# greedy_large.net
KiCad netlist of a schematic drawn in EAGLE
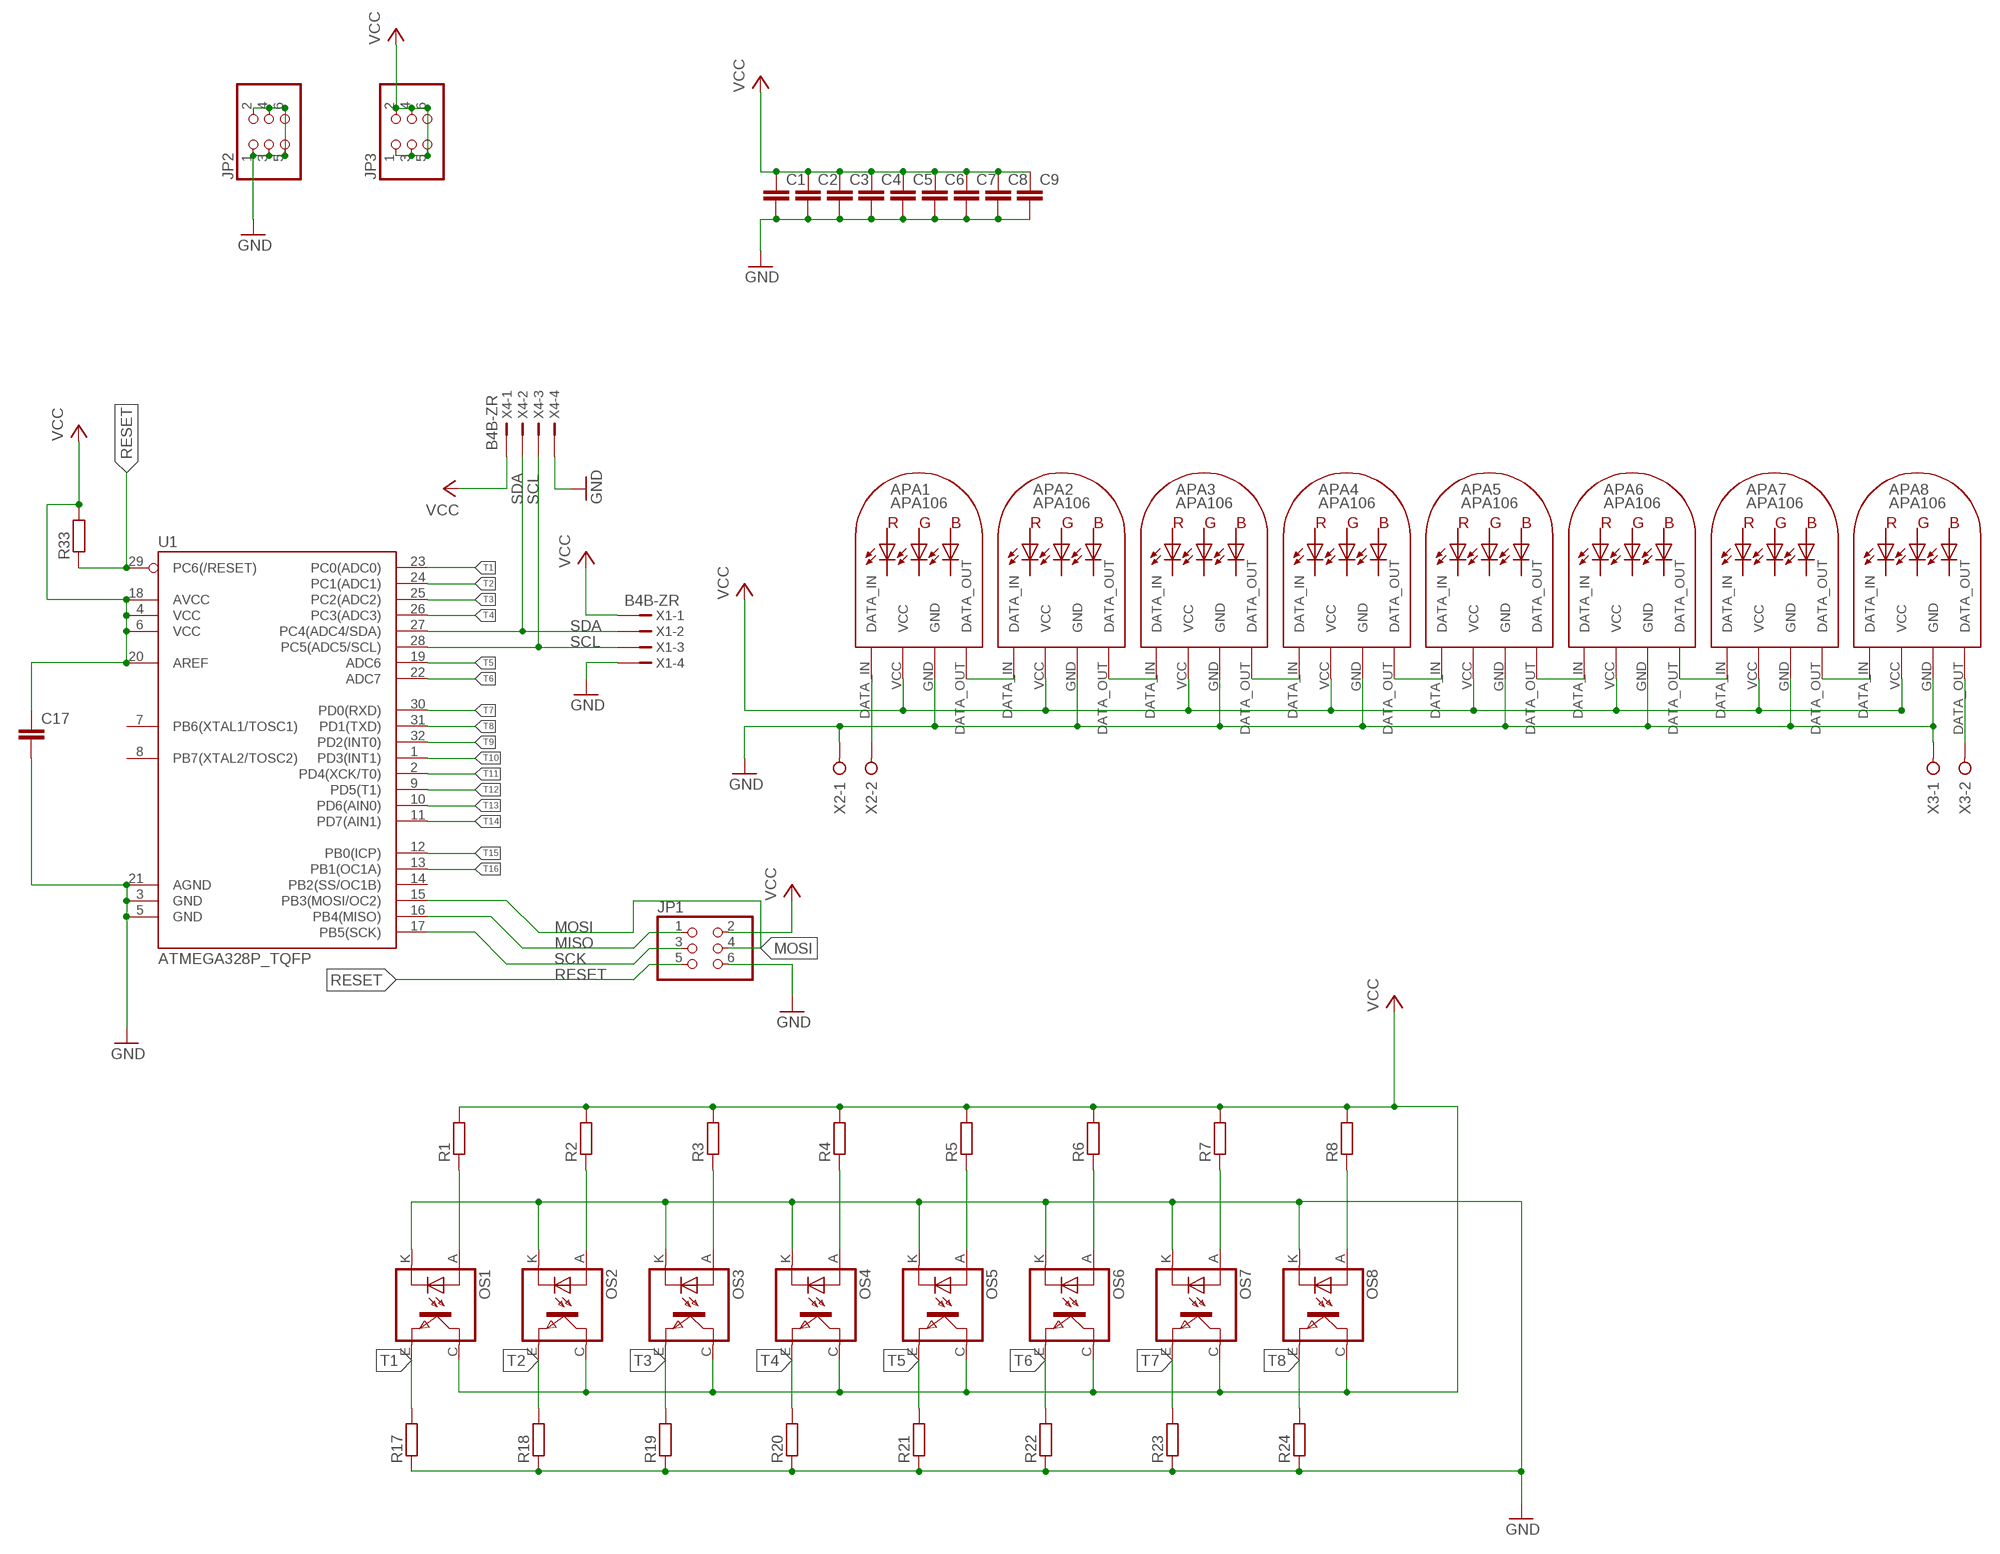
[diagram p0: schematic, sheet 1]

(export (version "E")
  (design (tool "Eeschema 10.0.6"))
  (components
    (comp (ref "APA1")
      (value "APA106")
      (footprint "eagle-import:APA_106_8MM")
      (libsource (lib "eagle-import") (part "APA106"))
    )
    (comp (ref "APA2")
      (value "APA106")
      (footprint "eagle-import:APA_106_8MM")
      (libsource (lib "eagle-import") (part "APA106"))
    )
    (comp (ref "APA3")
      (value "APA106")
      (footprint "eagle-import:APA_106_8MM")
      (libsource (lib "eagle-import") (part "APA106"))
    )
    (comp (ref "APA4")
      (value "APA106")
      (footprint "eagle-import:APA_106_8MM")
      (libsource (lib "eagle-import") (part "APA106"))
    )
    (comp (ref "APA5")
      (value "APA106")
      (footprint "eagle-import:APA_106_8MM")
      (libsource (lib "eagle-import") (part "APA106"))
    )
    (comp (ref "APA6")
      (value "APA106")
      (footprint "eagle-import:APA_106_8MM")
      (libsource (lib "eagle-import") (part "APA106"))
    )
    (comp (ref "APA7")
      (value "APA106")
      (footprint "eagle-import:APA_106_8MM")
      (libsource (lib "eagle-import") (part "APA106"))
    )
    (comp (ref "APA8")
      (value "APA106")
      (footprint "eagle-import:APA_106_8MM")
      (libsource (lib "eagle-import") (part "APA106"))
    )
    (comp (ref "C1")
      (value "C5/3")
      (footprint "eagle-import:C5B3")
      (libsource (lib "eagle-import") (part "C5/3"))
    )
    (comp (ref "C2")
      (value "C5/3")
      (footprint "eagle-import:C5B3")
      (libsource (lib "eagle-import") (part "C5/3"))
    )
    (comp (ref "C3")
      (value "C5/3")
      (footprint "eagle-import:C5B3")
      (libsource (lib "eagle-import") (part "C5/3"))
    )
    (comp (ref "C4")
      (value "C5/3")
      (footprint "eagle-import:C5B3")
      (libsource (lib "eagle-import") (part "C5/3"))
    )
    (comp (ref "C5")
      (value "C5/3")
      (footprint "eagle-import:C5B3")
      (libsource (lib "eagle-import") (part "C5/3"))
    )
    (comp (ref "C6")
      (value "C5/3")
      (footprint "eagle-import:C5B3")
      (libsource (lib "eagle-import") (part "C5/3"))
    )
    (comp (ref "C7")
      (value "C5/3")
      (footprint "eagle-import:C5B3")
      (libsource (lib "eagle-import") (part "C5/3"))
    )
    (comp (ref "C8")
      (value "C5/3")
      (footprint "eagle-import:C5B3")
      (libsource (lib "eagle-import") (part "C5/3"))
    )
    (comp (ref "C9")
      (value "C5/3")
      (footprint "eagle-import:C5B3")
      (libsource (lib "eagle-import") (part "C5/3"))
    )
    (comp (ref "C17")
      (value "C-EU025-025X050")
      (footprint "eagle-import:C025-025X050")
      (libsource (lib "eagle-import") (part "C-EU025-025X050"))
    )
    (comp (ref "JP1")
      (value "PINHD-2X3")
      (footprint "eagle-import:2X03")
      (libsource (lib "eagle-import") (part "PINHD-2X3"))
    )
    (comp (ref "JP2")
      (value "PINHD-2X3")
      (footprint "eagle-import:2X03")
      (libsource (lib "eagle-import") (part "PINHD-2X3"))
    )
    (comp (ref "JP3")
      (value "PINHD-2X3")
      (footprint "eagle-import:2X03")
      (libsource (lib "eagle-import") (part "PINHD-2X3"))
    )
    (comp (ref "OS1")
      (value "TCRT5000")
      (footprint "eagle-import:TCRT5000")
      (libsource (lib "eagle-import") (part "TCRT5000"))
    )
    (comp (ref "OS2")
      (value "TCRT5000")
      (footprint "eagle-import:TCRT5000")
      (libsource (lib "eagle-import") (part "TCRT5000"))
    )
    (comp (ref "OS3")
      (value "TCRT5000")
      (footprint "eagle-import:TCRT5000")
      (libsource (lib "eagle-import") (part "TCRT5000"))
    )
    (comp (ref "OS4")
      (value "TCRT5000")
      (footprint "eagle-import:TCRT5000")
      (libsource (lib "eagle-import") (part "TCRT5000"))
    )
    (comp (ref "OS5")
      (value "TCRT5000")
      (footprint "eagle-import:TCRT5000")
      (libsource (lib "eagle-import") (part "TCRT5000"))
    )
    (comp (ref "OS6")
      (value "TCRT5000")
      (footprint "eagle-import:TCRT5000")
      (libsource (lib "eagle-import") (part "TCRT5000"))
    )
    (comp (ref "OS7")
      (value "TCRT5000")
      (footprint "eagle-import:TCRT5000")
      (libsource (lib "eagle-import") (part "TCRT5000"))
    )
    (comp (ref "OS8")
      (value "TCRT5000")
      (footprint "eagle-import:TCRT5000")
      (libsource (lib "eagle-import") (part "TCRT5000"))
    )
    (comp (ref "R1")
      (value "R-EU_R0805")
      (footprint "eagle-import:R0805")
      (libsource (lib "eagle-import") (part "R-EU_R0805"))
    )
    (comp (ref "R2")
      (value "R-EU_R0805")
      (footprint "eagle-import:R0805")
      (libsource (lib "eagle-import") (part "R-EU_R0805"))
    )
    (comp (ref "R3")
      (value "R-EU_R0805")
      (footprint "eagle-import:R0805")
      (libsource (lib "eagle-import") (part "R-EU_R0805"))
    )
    (comp (ref "R4")
      (value "R-EU_R0805")
      (footprint "eagle-import:R0805")
      (libsource (lib "eagle-import") (part "R-EU_R0805"))
    )
    (comp (ref "R5")
      (value "R-EU_R0805")
      (footprint "eagle-import:R0805")
      (libsource (lib "eagle-import") (part "R-EU_R0805"))
    )
    (comp (ref "R6")
      (value "R-EU_R0805")
      (footprint "eagle-import:R0805")
      (libsource (lib "eagle-import") (part "R-EU_R0805"))
    )
    (comp (ref "R7")
      (value "R-EU_R0805")
      (footprint "eagle-import:R0805")
      (libsource (lib "eagle-import") (part "R-EU_R0805"))
    )
    (comp (ref "R8")
      (value "R-EU_R0805")
      (footprint "eagle-import:R0805")
      (libsource (lib "eagle-import") (part "R-EU_R0805"))
    )
    (comp (ref "R17")
      (value "R-EU_R0805")
      (footprint "eagle-import:R0805")
      (libsource (lib "eagle-import") (part "R-EU_R0805"))
    )
    (comp (ref "R18")
      (value "R-EU_R0805")
      (footprint "eagle-import:R0805")
      (libsource (lib "eagle-import") (part "R-EU_R0805"))
    )
    (comp (ref "R19")
      (value "R-EU_R0805")
      (footprint "eagle-import:R0805")
      (libsource (lib "eagle-import") (part "R-EU_R0805"))
    )
    (comp (ref "R20")
      (value "R-EU_R0805")
      (footprint "eagle-import:R0805")
      (libsource (lib "eagle-import") (part "R-EU_R0805"))
    )
    (comp (ref "R21")
      (value "R-EU_R0805")
      (footprint "eagle-import:R0805")
      (libsource (lib "eagle-import") (part "R-EU_R0805"))
    )
    (comp (ref "R22")
      (value "R-EU_R0805")
      (footprint "eagle-import:R0805")
      (libsource (lib "eagle-import") (part "R-EU_R0805"))
    )
    (comp (ref "R23")
      (value "R-EU_R0805")
      (footprint "eagle-import:R0805")
      (libsource (lib "eagle-import") (part "R-EU_R0805"))
    )
    (comp (ref "R24")
      (value "R-EU_R0805")
      (footprint "eagle-import:R0805")
      (libsource (lib "eagle-import") (part "R-EU_R0805"))
    )
    (comp (ref "R33")
      (value "R-EU_R0805")
      (footprint "eagle-import:R0805")
      (libsource (lib "eagle-import") (part "R-EU_R0805"))
    )
    (comp (ref "U1")
      (value "ATMEGA328P_TQFP")
      (footprint "eagle-import:TQFP32-08")
      (libsource (lib "eagle-import") (part "ATMEGA328P_TQFP"))
    )
    (comp (ref "X1")
      (value "B4B-ZR")
      (footprint "eagle-import:B4B-ZR")
      (fields (field (name "MF") "FARNELL") (field (name "MPN") "B4B-ZR(LF)(SN)"))
      (libsource (lib "eagle-import") (part "?4B-ZRB"))
    )
    (comp (ref "X2")
      (value "W237-02P")
      (footprint "eagle-import:W237-132")
      (libsource (lib "eagle-import") (part "W237-02P"))
    )
    (comp (ref "X3")
      (value "W237-02P")
      (footprint "eagle-import:W237-132")
      (libsource (lib "eagle-import") (part "W237-02P"))
    )
    (comp (ref "X4")
      (value "B4B-ZR")
      (footprint "eagle-import:B4B-ZR")
      (fields (field (name "MF") "FARNELL") (field (name "MPN") "B4B-ZR(LF)(SN)"))
      (libsource (lib "eagle-import") (part "?4B-ZRB"))
    )
  )
  (nets
    (net (code "1") (name "/MISO") (class "Default")
      (node (ref "JP1") (pin "1") (pinfunction "1_1") (pintype "passive"))
      (node (ref "U1") (pin "16") (pinfunction "PB4(MISO)_16") (pintype "bidirectional"))
    )
    (net (code "2") (name "/SCK") (class "Default")
      (node (ref "JP1") (pin "3") (pinfunction "3_3") (pintype "passive"))
      (node (ref "U1") (pin "17") (pinfunction "PB5(SCK)_17") (pintype "bidirectional"))
    )
    (net (code "3") (name "/SCL") (class "Default")
      (node (ref "U1") (pin "28") (pinfunction "PC5(ADC5/SCL)_28") (pintype "bidirectional"))
      (node (ref "X1") (pin "3") (pinfunction "1_3") (pintype "passive"))
      (node (ref "X4") (pin "3") (pinfunction "1_3") (pintype "passive"))
    )
    (net (code "4") (name "/SDA") (class "Default")
      (node (ref "U1") (pin "27") (pinfunction "PC4(ADC4/SDA)_27") (pintype "bidirectional"))
      (node (ref "X1") (pin "2") (pinfunction "1_2") (pintype "passive"))
      (node (ref "X4") (pin "2") (pinfunction "1_2") (pintype "passive"))
    )
    (net (code "5") (name "GND") (class "Default")
      (node (ref "APA1") (pin "GND") (pinfunction "GND_GND") (pintype "power_in"))
      (node (ref "APA2") (pin "GND") (pinfunction "GND_GND") (pintype "power_in"))
      (node (ref "APA3") (pin "GND") (pinfunction "GND_GND") (pintype "power_in"))
      (node (ref "APA4") (pin "GND") (pinfunction "GND_GND") (pintype "power_in"))
      (node (ref "APA5") (pin "GND") (pinfunction "GND_GND") (pintype "power_in"))
      (node (ref "APA6") (pin "GND") (pinfunction "GND_GND") (pintype "power_in"))
      (node (ref "APA7") (pin "GND") (pinfunction "GND_GND") (pintype "power_in"))
      (node (ref "APA8") (pin "GND") (pinfunction "GND_GND") (pintype "power_in"))
      (node (ref "C1") (pin "2") (pinfunction "2_2") (pintype "passive"))
      (node (ref "C17") (pin "2") (pinfunction "2_2") (pintype "passive"))
      (node (ref "C2") (pin "2") (pinfunction "2_2") (pintype "passive"))
      (node (ref "C3") (pin "2") (pinfunction "2_2") (pintype "passive"))
      (node (ref "C4") (pin "2") (pinfunction "2_2") (pintype "passive"))
      (node (ref "C5") (pin "2") (pinfunction "2_2") (pintype "passive"))
      (node (ref "C6") (pin "2") (pinfunction "2_2") (pintype "passive"))
      (node (ref "C7") (pin "2") (pinfunction "2_2") (pintype "passive"))
      (node (ref "C8") (pin "2") (pinfunction "2_2") (pintype "passive"))
      (node (ref "C9") (pin "2") (pinfunction "2_2") (pintype "passive"))
      (node (ref "JP1") (pin "6") (pinfunction "6_6") (pintype "passive"))
      (node (ref "JP2") (pin "1") (pinfunction "1_1") (pintype "passive"))
      (node (ref "JP2") (pin "2") (pinfunction "2_2") (pintype "passive"))
      (node (ref "JP2") (pin "3") (pinfunction "3_3") (pintype "passive"))
      (node (ref "JP2") (pin "4") (pinfunction "4_4") (pintype "passive"))
      (node (ref "JP2") (pin "5") (pinfunction "5_5") (pintype "passive"))
      (node (ref "JP2") (pin "6") (pinfunction "6_6") (pintype "passive"))
      (node (ref "OS1") (pin "K") (pinfunction "CATHODE_K") (pintype "passive"))
      (node (ref "OS2") (pin "K") (pinfunction "CATHODE_K") (pintype "passive"))
      (node (ref "OS3") (pin "K") (pinfunction "CATHODE_K") (pintype "passive"))
      (node (ref "OS4") (pin "K") (pinfunction "CATHODE_K") (pintype "passive"))
      (node (ref "OS5") (pin "K") (pinfunction "CATHODE_K") (pintype "passive"))
      (node (ref "OS6") (pin "K") (pinfunction "CATHODE_K") (pintype "passive"))
      (node (ref "OS7") (pin "K") (pinfunction "CATHODE_K") (pintype "passive"))
      (node (ref "OS8") (pin "K") (pinfunction "CATHODE_K") (pintype "passive"))
      (node (ref "R17") (pin "1") (pinfunction "1_1") (pintype "passive"))
      (node (ref "R17") (pin "11") (pinfunction "1_11") (pintype "passive"))
      (node (ref "R18") (pin "1") (pinfunction "1_1") (pintype "passive"))
      (node (ref "R18") (pin "11") (pinfunction "1_11") (pintype "passive"))
      (node (ref "R19") (pin "1") (pinfunction "1_1") (pintype "passive"))
      (node (ref "R19") (pin "11") (pinfunction "1_11") (pintype "passive"))
      (node (ref "R20") (pin "1") (pinfunction "1_1") (pintype "passive"))
      (node (ref "R20") (pin "11") (pinfunction "1_11") (pintype "passive"))
      (node (ref "R21") (pin "1") (pinfunction "1_1") (pintype "passive"))
      (node (ref "R21") (pin "11") (pinfunction "1_11") (pintype "passive"))
      (node (ref "R22") (pin "1") (pinfunction "1_1") (pintype "passive"))
      (node (ref "R22") (pin "11") (pinfunction "1_11") (pintype "passive"))
      (node (ref "R23") (pin "1") (pinfunction "1_1") (pintype "passive"))
      (node (ref "R23") (pin "11") (pinfunction "1_11") (pintype "passive"))
      (node (ref "R24") (pin "1") (pinfunction "1_1") (pintype "passive"))
      (node (ref "R24") (pin "11") (pinfunction "1_11") (pintype "passive"))
      (node (ref "U1") (pin "21") (pinfunction "AGND_21") (pintype "bidirectional"))
      (node (ref "U1") (pin "3") (pinfunction "GND_3") (pintype "bidirectional"))
      (node (ref "U1") (pin "5") (pinfunction "GND_5") (pintype "bidirectional"))
      (node (ref "X1") (pin "4") (pinfunction "1_4") (pintype "passive"))
      (node (ref "X2") (pin "1") (pinfunction "KL_1") (pintype "passive"))
      (node (ref "X3") (pin "1") (pinfunction "KL_1") (pintype "passive"))
      (node (ref "X4") (pin "4") (pinfunction "1_4") (pintype "passive"))
    )
    (net (code "6") (name "MOSI") (class "Default")
      (node (ref "JP1") (pin "4") (pinfunction "4_4") (pintype "passive"))
      (node (ref "U1") (pin "15") (pinfunction "PB3(MOSI/OC2)_15") (pintype "bidirectional"))
    )
    (net (code "7") (name "Net-(APA1-PadDATA_OUT)") (class "Default")
      (node (ref "APA1") (pin "DATA_OUT") (pinfunction "DATA_OUT_DATA_OUT") (pintype "bidirectional"))
      (node (ref "APA2") (pin "DATA_IN") (pinfunction "DATA_IN_DATA_IN") (pintype "bidirectional"))
    )
    (net (code "8") (name "Net-(APA2-PadDATA_OUT)") (class "Default")
      (node (ref "APA2") (pin "DATA_OUT") (pinfunction "DATA_OUT_DATA_OUT") (pintype "bidirectional"))
      (node (ref "APA3") (pin "DATA_IN") (pinfunction "DATA_IN_DATA_IN") (pintype "bidirectional"))
    )
    (net (code "9") (name "Net-(APA3-PadDATA_OUT)") (class "Default")
      (node (ref "APA3") (pin "DATA_OUT") (pinfunction "DATA_OUT_DATA_OUT") (pintype "bidirectional"))
      (node (ref "APA4") (pin "DATA_IN") (pinfunction "DATA_IN_DATA_IN") (pintype "bidirectional"))
    )
    (net (code "10") (name "Net-(APA4-PadDATA_OUT)") (class "Default")
      (node (ref "APA4") (pin "DATA_OUT") (pinfunction "DATA_OUT_DATA_OUT") (pintype "bidirectional"))
      (node (ref "APA5") (pin "DATA_IN") (pinfunction "DATA_IN_DATA_IN") (pintype "bidirectional"))
    )
    (net (code "11") (name "Net-(APA5-PadDATA_OUT)") (class "Default")
      (node (ref "APA5") (pin "DATA_OUT") (pinfunction "DATA_OUT_DATA_OUT") (pintype "bidirectional"))
      (node (ref "APA6") (pin "DATA_IN") (pinfunction "DATA_IN_DATA_IN") (pintype "bidirectional"))
    )
    (net (code "12") (name "Net-(APA6-PadDATA_OUT)") (class "Default")
      (node (ref "APA6") (pin "DATA_OUT") (pinfunction "DATA_OUT_DATA_OUT") (pintype "bidirectional"))
      (node (ref "APA7") (pin "DATA_IN") (pinfunction "DATA_IN_DATA_IN") (pintype "bidirectional"))
    )
    (net (code "13") (name "Net-(APA7-PadDATA_OUT)") (class "Default")
      (node (ref "APA7") (pin "DATA_OUT") (pinfunction "DATA_OUT_DATA_OUT") (pintype "bidirectional"))
      (node (ref "APA8") (pin "DATA_IN") (pinfunction "DATA_IN_DATA_IN") (pintype "bidirectional"))
    )
    (net (code "14") (name "Net-(OS1-ANODE)") (class "Default")
      (node (ref "OS1") (pin "A") (pinfunction "ANODE_A") (pintype "passive"))
      (node (ref "R1") (pin "1") (pinfunction "1_1") (pintype "passive"))
      (node (ref "R1") (pin "11") (pinfunction "1_11") (pintype "passive"))
    )
    (net (code "15") (name "Net-(OS2-ANODE)") (class "Default")
      (node (ref "OS2") (pin "A") (pinfunction "ANODE_A") (pintype "passive"))
      (node (ref "R2") (pin "1") (pinfunction "1_1") (pintype "passive"))
      (node (ref "R2") (pin "11") (pinfunction "1_11") (pintype "passive"))
    )
    (net (code "16") (name "Net-(OS3-ANODE)") (class "Default")
      (node (ref "OS3") (pin "A") (pinfunction "ANODE_A") (pintype "passive"))
      (node (ref "R3") (pin "1") (pinfunction "1_1") (pintype "passive"))
      (node (ref "R3") (pin "11") (pinfunction "1_11") (pintype "passive"))
    )
    (net (code "17") (name "Net-(OS4-ANODE)") (class "Default")
      (node (ref "OS4") (pin "A") (pinfunction "ANODE_A") (pintype "passive"))
      (node (ref "R4") (pin "1") (pinfunction "1_1") (pintype "passive"))
      (node (ref "R4") (pin "11") (pinfunction "1_11") (pintype "passive"))
    )
    (net (code "18") (name "Net-(OS5-ANODE)") (class "Default")
      (node (ref "OS5") (pin "A") (pinfunction "ANODE_A") (pintype "passive"))
      (node (ref "R5") (pin "1") (pinfunction "1_1") (pintype "passive"))
      (node (ref "R5") (pin "11") (pinfunction "1_11") (pintype "passive"))
    )
    (net (code "19") (name "Net-(OS6-ANODE)") (class "Default")
      (node (ref "OS6") (pin "A") (pinfunction "ANODE_A") (pintype "passive"))
      (node (ref "R6") (pin "1") (pinfunction "1_1") (pintype "passive"))
      (node (ref "R6") (pin "11") (pinfunction "1_11") (pintype "passive"))
    )
    (net (code "20") (name "Net-(OS7-ANODE)") (class "Default")
      (node (ref "OS7") (pin "A") (pinfunction "ANODE_A") (pintype "passive"))
      (node (ref "R7") (pin "1") (pinfunction "1_1") (pintype "passive"))
      (node (ref "R7") (pin "11") (pinfunction "1_11") (pintype "passive"))
    )
    (net (code "21") (name "Net-(OS8-ANODE)") (class "Default")
      (node (ref "OS8") (pin "A") (pinfunction "ANODE_A") (pintype "passive"))
      (node (ref "R8") (pin "1") (pinfunction "1_1") (pintype "passive"))
      (node (ref "R8") (pin "11") (pinfunction "1_11") (pintype "passive"))
    )
    (net (code "22") (name "Net-(X2B-KL)") (class "Default")
      (node (ref "APA1") (pin "DATA_IN") (pinfunction "DATA_IN_DATA_IN") (pintype "bidirectional"))
      (node (ref "X2") (pin "2") (pinfunction "KL_2") (pintype "passive"))
    )
    (net (code "23") (name "Net-(X3B-KL)") (class "Default")
      (node (ref "APA8") (pin "DATA_OUT") (pinfunction "DATA_OUT_DATA_OUT") (pintype "bidirectional"))
      (node (ref "X3") (pin "2") (pinfunction "KL_2") (pintype "passive"))
    )
    (net (code "24") (name "RESET") (class "Default")
      (node (ref "JP1") (pin "5") (pinfunction "5_5") (pintype "passive"))
      (node (ref "R33") (pin "1") (pinfunction "1_1") (pintype "passive"))
      (node (ref "R33") (pin "11") (pinfunction "1_11") (pintype "passive"))
      (node (ref "U1") (pin "29") (pinfunction "PC6(/RESET)_29") (pintype "bidirectional"))
    )
    (net (code "25") (name "T1") (class "Default")
      (node (ref "OS1") (pin "E") (pinfunction "EMITTER_E") (pintype "passive"))
      (node (ref "R17") (pin "2") (pinfunction "2_2") (pintype "passive"))
      (node (ref "R17") (pin "21") (pinfunction "2_21") (pintype "passive"))
      (node (ref "U1") (pin "23") (pinfunction "PC0(ADC0)_23") (pintype "bidirectional"))
    )
    (net (code "26") (name "T2") (class "Default")
      (node (ref "OS2") (pin "E") (pinfunction "EMITTER_E") (pintype "passive"))
      (node (ref "R18") (pin "2") (pinfunction "2_2") (pintype "passive"))
      (node (ref "R18") (pin "21") (pinfunction "2_21") (pintype "passive"))
      (node (ref "U1") (pin "24") (pinfunction "PC1(ADC1)_24") (pintype "bidirectional"))
    )
    (net (code "27") (name "T3") (class "Default")
      (node (ref "OS3") (pin "E") (pinfunction "EMITTER_E") (pintype "passive"))
      (node (ref "R19") (pin "2") (pinfunction "2_2") (pintype "passive"))
      (node (ref "R19") (pin "21") (pinfunction "2_21") (pintype "passive"))
      (node (ref "U1") (pin "25") (pinfunction "PC2(ADC2)_25") (pintype "bidirectional"))
    )
    (net (code "28") (name "T4") (class "Default")
      (node (ref "OS4") (pin "E") (pinfunction "EMITTER_E") (pintype "passive"))
      (node (ref "R20") (pin "2") (pinfunction "2_2") (pintype "passive"))
      (node (ref "R20") (pin "21") (pinfunction "2_21") (pintype "passive"))
      (node (ref "U1") (pin "26") (pinfunction "PC3(ADC3)_26") (pintype "bidirectional"))
    )
    (net (code "29") (name "T5") (class "Default")
      (node (ref "OS5") (pin "E") (pinfunction "EMITTER_E") (pintype "passive"))
      (node (ref "R21") (pin "2") (pinfunction "2_2") (pintype "passive"))
      (node (ref "R21") (pin "21") (pinfunction "2_21") (pintype "passive"))
      (node (ref "U1") (pin "19") (pinfunction "ADC6_19") (pintype "bidirectional"))
    )
    (net (code "30") (name "T6") (class "Default")
      (node (ref "OS6") (pin "E") (pinfunction "EMITTER_E") (pintype "passive"))
      (node (ref "R22") (pin "2") (pinfunction "2_2") (pintype "passive"))
      (node (ref "R22") (pin "21") (pinfunction "2_21") (pintype "passive"))
      (node (ref "U1") (pin "22") (pinfunction "ADC7_22") (pintype "bidirectional"))
    )
    (net (code "31") (name "T7") (class "Default")
      (node (ref "OS7") (pin "E") (pinfunction "EMITTER_E") (pintype "passive"))
      (node (ref "R23") (pin "2") (pinfunction "2_2") (pintype "passive"))
      (node (ref "R23") (pin "21") (pinfunction "2_21") (pintype "passive"))
      (node (ref "U1") (pin "30") (pinfunction "PD0(RXD)_30") (pintype "bidirectional"))
    )
    (net (code "32") (name "T8") (class "Default")
      (node (ref "OS8") (pin "E") (pinfunction "EMITTER_E") (pintype "passive"))
      (node (ref "R24") (pin "2") (pinfunction "2_2") (pintype "passive"))
      (node (ref "R24") (pin "21") (pinfunction "2_21") (pintype "passive"))
      (node (ref "U1") (pin "31") (pinfunction "PD1(TXD)_31") (pintype "bidirectional"))
    )
    (net (code "33") (name "T9") (class "Default")
      (node (ref "U1") (pin "32") (pinfunction "PD2(INT0)_32") (pintype "bidirectional"))
    )
    (net (code "34") (name "T10") (class "Default")
      (node (ref "U1") (pin "1") (pinfunction "PD3(INT1)_1") (pintype "bidirectional"))
    )
    (net (code "35") (name "T11") (class "Default")
      (node (ref "U1") (pin "2") (pinfunction "PD4(XCK/T0)_2") (pintype "bidirectional"))
    )
    (net (code "36") (name "T12") (class "Default")
      (node (ref "U1") (pin "9") (pinfunction "PD5(T1)_9") (pintype "bidirectional"))
    )
    (net (code "37") (name "T13") (class "Default")
      (node (ref "U1") (pin "10") (pinfunction "PD6(AIN0)_10") (pintype "bidirectional"))
    )
    (net (code "38") (name "T14") (class "Default")
      (node (ref "U1") (pin "11") (pinfunction "PD7(AIN1)_11") (pintype "bidirectional"))
    )
    (net (code "39") (name "T15") (class "Default")
      (node (ref "U1") (pin "12") (pinfunction "PB0(ICP)_12") (pintype "bidirectional"))
    )
    (net (code "40") (name "T16") (class "Default")
      (node (ref "U1") (pin "13") (pinfunction "PB1(OC1A)_13") (pintype "bidirectional"))
    )
    (net (code "41") (name "VCC") (class "Default")
      (node (ref "APA1") (pin "VCC") (pinfunction "VCC_VCC") (pintype "power_in"))
      (node (ref "APA2") (pin "VCC") (pinfunction "VCC_VCC") (pintype "power_in"))
      (node (ref "APA3") (pin "VCC") (pinfunction "VCC_VCC") (pintype "power_in"))
      (node (ref "APA4") (pin "VCC") (pinfunction "VCC_VCC") (pintype "power_in"))
      (node (ref "APA5") (pin "VCC") (pinfunction "VCC_VCC") (pintype "power_in"))
      (node (ref "APA6") (pin "VCC") (pinfunction "VCC_VCC") (pintype "power_in"))
      (node (ref "APA7") (pin "VCC") (pinfunction "VCC_VCC") (pintype "power_in"))
      (node (ref "APA8") (pin "VCC") (pinfunction "VCC_VCC") (pintype "power_in"))
      (node (ref "C1") (pin "1") (pinfunction "1_1") (pintype "passive"))
      (node (ref "C17") (pin "1") (pinfunction "1_1") (pintype "passive"))
      (node (ref "C2") (pin "1") (pinfunction "1_1") (pintype "passive"))
      (node (ref "C3") (pin "1") (pinfunction "1_1") (pintype "passive"))
      (node (ref "C4") (pin "1") (pinfunction "1_1") (pintype "passive"))
      (node (ref "C5") (pin "1") (pinfunction "1_1") (pintype "passive"))
      (node (ref "C6") (pin "1") (pinfunction "1_1") (pintype "passive"))
      (node (ref "C7") (pin "1") (pinfunction "1_1") (pintype "passive"))
      (node (ref "C8") (pin "1") (pinfunction "1_1") (pintype "passive"))
      (node (ref "C9") (pin "1") (pinfunction "1_1") (pintype "passive"))
      (node (ref "JP1") (pin "2") (pinfunction "2_2") (pintype "passive"))
      (node (ref "JP3") (pin "1") (pinfunction "1_1") (pintype "passive"))
      (node (ref "JP3") (pin "2") (pinfunction "2_2") (pintype "passive"))
      (node (ref "JP3") (pin "3") (pinfunction "3_3") (pintype "passive"))
      (node (ref "JP3") (pin "4") (pinfunction "4_4") (pintype "passive"))
      (node (ref "JP3") (pin "5") (pinfunction "5_5") (pintype "passive"))
      (node (ref "JP3") (pin "6") (pinfunction "6_6") (pintype "passive"))
      (node (ref "OS1") (pin "C") (pinfunction "COLLECTOR_C") (pintype "passive"))
      (node (ref "OS2") (pin "C") (pinfunction "COLLECTOR_C") (pintype "passive"))
      (node (ref "OS3") (pin "C") (pinfunction "COLLECTOR_C") (pintype "passive"))
      (node (ref "OS4") (pin "C") (pinfunction "COLLECTOR_C") (pintype "passive"))
      (node (ref "OS5") (pin "C") (pinfunction "COLLECTOR_C") (pintype "passive"))
      (node (ref "OS6") (pin "C") (pinfunction "COLLECTOR_C") (pintype "passive"))
      (node (ref "OS7") (pin "C") (pinfunction "COLLECTOR_C") (pintype "passive"))
      (node (ref "OS8") (pin "C") (pinfunction "COLLECTOR_C") (pintype "passive"))
      (node (ref "R1") (pin "2") (pinfunction "2_2") (pintype "passive"))
      (node (ref "R1") (pin "21") (pinfunction "2_21") (pintype "passive"))
      (node (ref "R2") (pin "2") (pinfunction "2_2") (pintype "passive"))
      (node (ref "R2") (pin "21") (pinfunction "2_21") (pintype "passive"))
      (node (ref "R3") (pin "2") (pinfunction "2_2") (pintype "passive"))
      (node (ref "R3") (pin "21") (pinfunction "2_21") (pintype "passive"))
      (node (ref "R33") (pin "2") (pinfunction "2_2") (pintype "passive"))
      (node (ref "R33") (pin "21") (pinfunction "2_21") (pintype "passive"))
      (node (ref "R4") (pin "2") (pinfunction "2_2") (pintype "passive"))
      (node (ref "R4") (pin "21") (pinfunction "2_21") (pintype "passive"))
      (node (ref "R5") (pin "2") (pinfunction "2_2") (pintype "passive"))
      (node (ref "R5") (pin "21") (pinfunction "2_21") (pintype "passive"))
      (node (ref "R6") (pin "2") (pinfunction "2_2") (pintype "passive"))
      (node (ref "R6") (pin "21") (pinfunction "2_21") (pintype "passive"))
      (node (ref "R7") (pin "2") (pinfunction "2_2") (pintype "passive"))
      (node (ref "R7") (pin "21") (pinfunction "2_21") (pintype "passive"))
      (node (ref "R8") (pin "2") (pinfunction "2_2") (pintype "passive"))
      (node (ref "R8") (pin "21") (pinfunction "2_21") (pintype "passive"))
      (node (ref "U1") (pin "18") (pinfunction "AVCC_18") (pintype "bidirectional"))
      (node (ref "U1") (pin "20") (pinfunction "AREF_20") (pintype "bidirectional"))
      (node (ref "U1") (pin "4") (pinfunction "VCC_4") (pintype "bidirectional"))
      (node (ref "U1") (pin "6") (pinfunction "VCC_6") (pintype "bidirectional"))
      (node (ref "X1") (pin "1") (pinfunction "1_1") (pintype "passive"))
      (node (ref "X4") (pin "1") (pinfunction "1_1") (pintype "passive"))
    )
    (net (code "42") (name "unconnected-(U1-PB2(SS{slash}OC1B)-Pad14)") (class "Default")
      (node (ref "U1") (pin "14") (pinfunction "PB2(SS/OC1B)_14") (pintype "bidirectional"))
    )
    (net (code "43") (name "unconnected-(U1-PB6(XTAL1{slash}TOSC1)-Pad7)") (class "Default")
      (node (ref "U1") (pin "7") (pinfunction "PB6(XTAL1/TOSC1)_7") (pintype "bidirectional"))
    )
    (net (code "44") (name "unconnected-(U1-PB7(XTAL2{slash}TOSC2)-Pad8)") (class "Default")
      (node (ref "U1") (pin "8") (pinfunction "PB7(XTAL2/TOSC2)_8") (pintype "bidirectional"))
    )
  )
)
